# gesamt.net
KiCad netlist of a schematic drawn in EAGLE
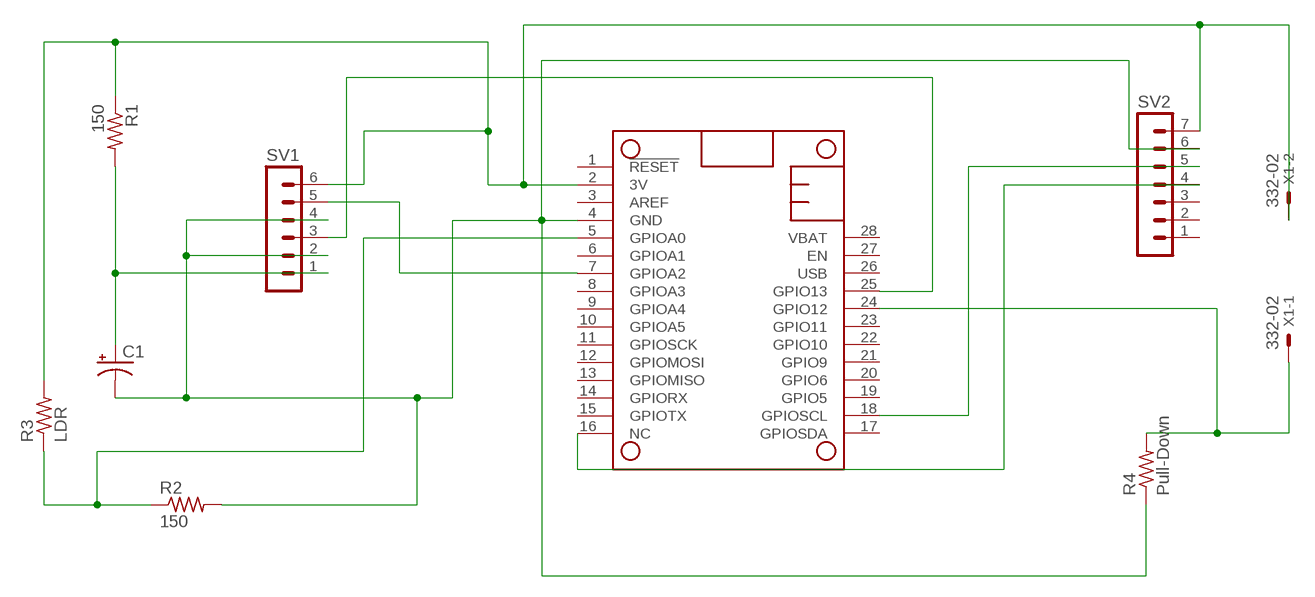
[diagram p0: schematic, sheet 1]

(export (version "E")
  (design (tool "Eeschema 10.0.6"))
  (components
    (comp (ref "C1")
      (value "CPOL-USE2,5-6E")
      (footprint "eagle-import:E2,5-6E")
      (libsource (lib "eagle-import") (part "CPOL-USE2,5-6E"))
    )
    (comp (ref "MS1")
      (value "FEATHERWING")
      (footprint "eagle-import:FEATHERWING")
      (libsource (lib "eagle-import") (part "FEATHERWING"))
    )
    (comp (ref "R1")
      (value "150")
      (footprint "eagle-import:0207_10")
      (libsource (lib "eagle-import") (part "R-US_0207/10"))
    )
    (comp (ref "R2")
      (value "150")
      (footprint "eagle-import:0207_10")
      (libsource (lib "eagle-import") (part "R-US_0207/10"))
    )
    (comp (ref "R3")
      (value "LDR")
      (footprint "eagle-import:V234_12")
      (libsource (lib "eagle-import") (part "R-US_V234/12"))
    )
    (comp (ref "R4")
      (value "Pull-Down")
      (footprint "eagle-import:0207_10")
      (libsource (lib "eagle-import") (part "R-US_0207/10"))
    )
    (comp (ref "SV1")
      (value "MA06-1")
      (footprint "eagle-import:MA06-1")
      (libsource (lib "eagle-import") (part "MA06-1"))
    )
    (comp (ref "SV2")
      (value "MA07-1")
      (footprint "eagle-import:MA07-1")
      (libsource (lib "eagle-import") (part "MA07-1"))
    )
    (comp (ref "X1")
      (value "332-02")
      (footprint "eagle-import:332-02")
      (libsource (lib "eagle-import") (part "332-02"))
    )
  )
  (nets
    (net (code "1") (name "/USB") (class "Default")
      (node (ref "MS1") (pin "26") (pinfunction "USB_26") (pintype "power_in"))
    )
    (net (code "2") (name "/VBAT") (class "Default")
      (node (ref "MS1") (pin "28") (pinfunction "VBAT_28") (pintype "power_in"))
    )
    (net (code "3") (name "Net-(C1-Pad+)") (class "Default")
      (node (ref "C1") (pin "+") (pinfunction "+_+") (pintype "passive"))
      (node (ref "R1") (pin "2") (pinfunction "2_2") (pintype "passive"))
      (node (ref "SV1") (pin "1") (pinfunction "1_1") (pintype "passive"))
    )
    (net (code "4") (name "Net-(MS1-3V)") (class "Default")
      (node (ref "MS1") (pin "2") (pinfunction "3V_2") (pintype "power_in"))
      (node (ref "R1") (pin "1") (pinfunction "1_1") (pintype "passive"))
      (node (ref "R3") (pin "2") (pinfunction "2_2") (pintype "passive"))
      (node (ref "SV1") (pin "6") (pinfunction "6_6") (pintype "passive"))
      (node (ref "SV2") (pin "7") (pinfunction "7_7") (pintype "passive"))
      (node (ref "X1") (pin "2") (pinfunction "S_2") (pintype "passive"))
    )
    (net (code "5") (name "Net-(MS1-GND)") (class "Default")
      (node (ref "C1") (pin "-") (pinfunction "-_-") (pintype "passive"))
      (node (ref "MS1") (pin "4") (pinfunction "GND_4") (pintype "power_in"))
      (node (ref "R2") (pin "2") (pinfunction "2_2") (pintype "passive"))
      (node (ref "R4") (pin "1") (pinfunction "1_1") (pintype "passive"))
      (node (ref "SV1") (pin "2") (pinfunction "2_2") (pintype "passive"))
      (node (ref "SV1") (pin "4") (pinfunction "4_4") (pintype "passive"))
      (node (ref "SV2") (pin "6") (pinfunction "6_6") (pintype "passive"))
    )
    (net (code "6") (name "Net-(MS1-GPIO12)") (class "Default")
      (node (ref "MS1") (pin "24") (pinfunction "GPIO12_24") (pintype "bidirectional"))
      (node (ref "R4") (pin "2") (pinfunction "2_2") (pintype "passive"))
      (node (ref "X1") (pin "1") (pinfunction "S_1") (pintype "passive"))
    )
    (net (code "7") (name "Net-(MS1-GPIO13)") (class "Default")
      (node (ref "MS1") (pin "25") (pinfunction "GPIO13_25") (pintype "bidirectional"))
      (node (ref "SV1") (pin "3") (pinfunction "3_3") (pintype "passive"))
    )
    (net (code "8") (name "Net-(MS1-GPIOA0)") (class "Default")
      (node (ref "MS1") (pin "5") (pinfunction "GPIOA0_5") (pintype "bidirectional"))
      (node (ref "R2") (pin "1") (pinfunction "1_1") (pintype "passive"))
      (node (ref "R3") (pin "1") (pinfunction "1_1") (pintype "passive"))
    )
    (net (code "9") (name "Net-(MS1-GPIOA2)") (class "Default")
      (node (ref "MS1") (pin "7") (pinfunction "GPIOA2_7") (pintype "bidirectional"))
      (node (ref "SV1") (pin "5") (pinfunction "5_5") (pintype "passive"))
    )
    (net (code "10") (name "Net-(MS1-GPIOSCL)") (class "Default")
      (node (ref "MS1") (pin "18") (pinfunction "GPIOSCL_18") (pintype "bidirectional"))
      (node (ref "SV2") (pin "5") (pinfunction "5_5") (pintype "passive"))
    )
    (net (code "11") (name "Net-(MS1-NC)") (class "Default")
      (node (ref "MS1") (pin "16") (pinfunction "NC_16") (pintype "passive"))
      (node (ref "SV2") (pin "4") (pinfunction "4_4") (pintype "passive"))
    )
    (net (code "12") (name "unconnected-(MS1-AREF-Pad3)") (class "Default")
      (node (ref "MS1") (pin "3") (pinfunction "AREF_3") (pintype "passive"))
    )
    (net (code "13") (name "unconnected-(MS1-EN-Pad27)") (class "Default")
      (node (ref "MS1") (pin "27") (pinfunction "EN_27") (pintype "passive"))
    )
    (net (code "14") (name "unconnected-(MS1-GPIO5-Pad19)") (class "Default")
      (node (ref "MS1") (pin "19") (pinfunction "GPIO5_19") (pintype "bidirectional"))
    )
    (net (code "15") (name "unconnected-(MS1-GPIO6-Pad20)") (class "Default")
      (node (ref "MS1") (pin "20") (pinfunction "GPIO6_20") (pintype "bidirectional"))
    )
    (net (code "16") (name "unconnected-(MS1-GPIO9-Pad21)") (class "Default")
      (node (ref "MS1") (pin "21") (pinfunction "GPIO9_21") (pintype "bidirectional"))
    )
    (net (code "17") (name "unconnected-(MS1-GPIO10-Pad22)") (class "Default")
      (node (ref "MS1") (pin "22") (pinfunction "GPIO10_22") (pintype "bidirectional"))
    )
    (net (code "18") (name "unconnected-(MS1-GPIO11-Pad23)") (class "Default")
      (node (ref "MS1") (pin "23") (pinfunction "GPIO11_23") (pintype "bidirectional"))
    )
    (net (code "19") (name "unconnected-(MS1-GPIOA1-Pad6)") (class "Default")
      (node (ref "MS1") (pin "6") (pinfunction "GPIOA1_6") (pintype "bidirectional"))
    )
    (net (code "20") (name "unconnected-(MS1-GPIOA3-Pad8)") (class "Default")
      (node (ref "MS1") (pin "8") (pinfunction "GPIOA3_8") (pintype "bidirectional"))
    )
    (net (code "21") (name "unconnected-(MS1-GPIOA4-Pad9)") (class "Default")
      (node (ref "MS1") (pin "9") (pinfunction "GPIOA4_9") (pintype "bidirectional"))
    )
    (net (code "22") (name "unconnected-(MS1-GPIOA5-Pad10)") (class "Default")
      (node (ref "MS1") (pin "10") (pinfunction "GPIOA5_10") (pintype "bidirectional"))
    )
    (net (code "23") (name "unconnected-(MS1-GPIOMISO-Pad13)") (class "Default")
      (node (ref "MS1") (pin "13") (pinfunction "GPIOMISO_13") (pintype "bidirectional"))
    )
    (net (code "24") (name "unconnected-(MS1-GPIOMOSI-Pad12)") (class "Default")
      (node (ref "MS1") (pin "12") (pinfunction "GPIOMOSI_12") (pintype "bidirectional"))
    )
    (net (code "25") (name "unconnected-(MS1-GPIORX-Pad14)") (class "Default")
      (node (ref "MS1") (pin "14") (pinfunction "GPIORX_14") (pintype "bidirectional"))
    )
    (net (code "26") (name "unconnected-(MS1-GPIOSCK-Pad11)") (class "Default")
      (node (ref "MS1") (pin "11") (pinfunction "GPIOSCK_11") (pintype "bidirectional"))
    )
    (net (code "27") (name "unconnected-(MS1-GPIOSDA-Pad17)") (class "Default")
      (node (ref "MS1") (pin "17") (pinfunction "GPIOSDA_17") (pintype "bidirectional"))
    )
    (net (code "28") (name "unconnected-(MS1-GPIOTX-Pad15)") (class "Default")
      (node (ref "MS1") (pin "15") (pinfunction "GPIOTX_15") (pintype "bidirectional"))
    )
    (net (code "29") (name "unconnected-(MS1-~{RESET}-Pad1)") (class "Default")
      (node (ref "MS1") (pin "1") (pinfunction "~{RESET}_1") (pintype "input"))
    )
    (net (code "30") (name "unconnected-(SV2-Pad1)") (class "Default")
      (node (ref "SV2") (pin "1") (pinfunction "1_1") (pintype "passive"))
    )
    (net (code "31") (name "unconnected-(SV2-Pad2)") (class "Default")
      (node (ref "SV2") (pin "2") (pinfunction "2_2") (pintype "passive"))
    )
    (net (code "32") (name "unconnected-(SV2-Pad3)") (class "Default")
      (node (ref "SV2") (pin "3") (pinfunction "3_3") (pintype "passive"))
    )
  )
)
